# nomux1_2.net
KiCad netlist of a schematic drawn in EAGLE
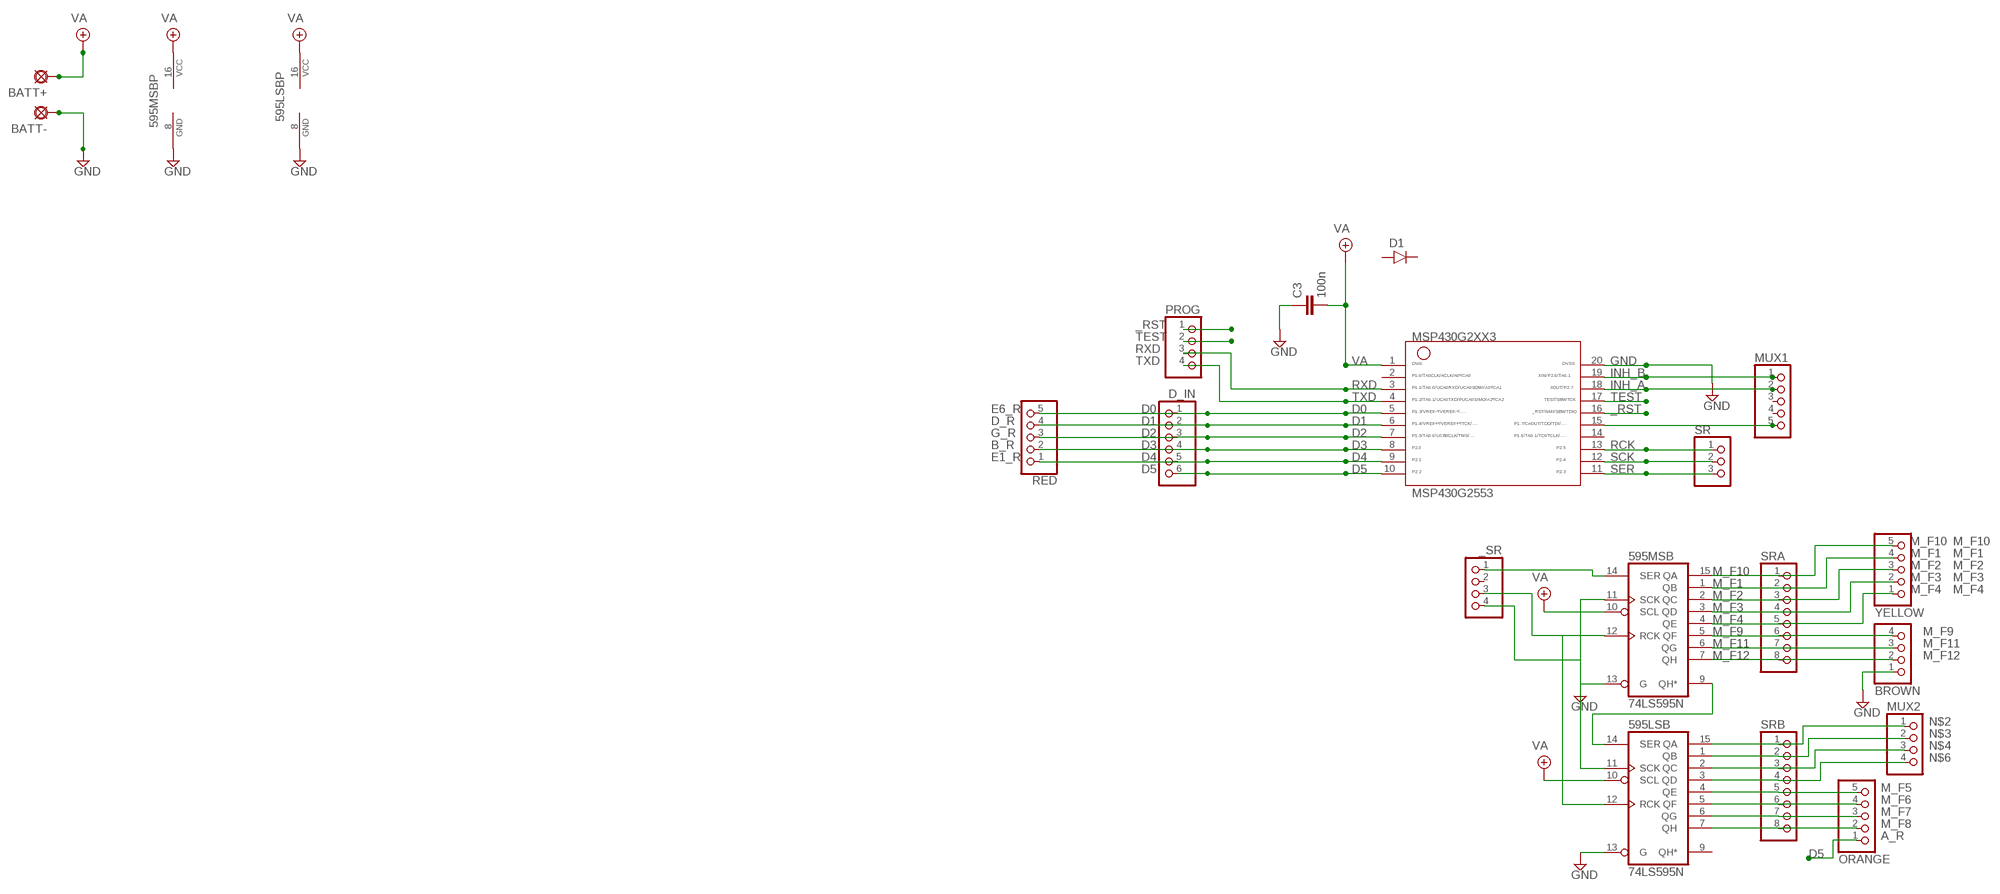
[diagram p0: schematic, sheet 1]

(export (version "E")
  (design (tool "Eeschema 10.0.6"))
  (components
    (comp (ref "595LSB")
      (value "74LS595N")
      (footprint "eagle-import:DIL16")
      (libsource (lib "eagle-import") (part "74595NLS"))
    )
    (comp (ref "595MSB")
      (value "74LS595N")
      (footprint "eagle-import:DIL16")
      (libsource (lib "eagle-import") (part "74595NLS"))
    )
    (comp (ref "BATT+")
      (value "PADL")
      (footprint "eagle-import:LONG")
      (libsource (lib "eagle-import") (part "PADL"))
    )
    (comp (ref "BATT-")
      (value "PADL")
      (footprint "eagle-import:LONG")
      (libsource (lib "eagle-import") (part "PADL"))
    )
    (comp (ref "BROWN")
      (value "PINHD-1X4")
      (footprint "eagle-import:1X04")
      (libsource (lib "eagle-import") (part "PINHD-1X4"))
    )
    (comp (ref "C3")
      (value "100n")
      (footprint "eagle-import:050X030_050_3")
      (libsource (lib "eagle-import") (part "050X030_050"))
    )
    (comp (ref "D1")
      (value "1N400X.4")
      (footprint "eagle-import:DO41-4")
      (libsource (lib "eagle-import") (part "1N400X.4"))
    )
    (comp (ref "D_IN")
      (value "PINHD-1X6")
      (footprint "eagle-import:1X06")
      (libsource (lib "eagle-import") (part "PINHD-1X6"))
    )
    (comp (ref "MSP430G2553")
      (value "G2XX3---N20")
      (footprint "eagle-import:N20")
      (libsource (lib "eagle-import") (part "G2XX3---N20"))
    )
    (comp (ref "MUX1")
      (value "PINHD-1X5")
      (footprint "eagle-import:1X05")
      (libsource (lib "eagle-import") (part "PINHD-1X5"))
    )
    (comp (ref "MUX2")
      (value "PINHD-1X4")
      (footprint "eagle-import:1X04")
      (libsource (lib "eagle-import") (part "PINHD-1X4"))
    )
    (comp (ref "ORANGE")
      (value "PINHD-1X5")
      (footprint "eagle-import:1X05")
      (libsource (lib "eagle-import") (part "PINHD-1X5"))
    )
    (comp (ref "PROG")
      (value "PINHD-1X4")
      (footprint "eagle-import:1X04")
      (libsource (lib "eagle-import") (part "PINHD-1X4"))
    )
    (comp (ref "RED")
      (value "PINHD-1X5")
      (footprint "eagle-import:1X05")
      (libsource (lib "eagle-import") (part "PINHD-1X5"))
    )
    (comp (ref "SR")
      (value "PINHD-1X3")
      (footprint "eagle-import:1X03")
      (libsource (lib "eagle-import") (part "PINHD-1X3"))
    )
    (comp (ref "SRA")
      (value "PINHD-1X8")
      (footprint "eagle-import:1X08")
      (libsource (lib "eagle-import") (part "PINHD-1X8"))
    )
    (comp (ref "SRB")
      (value "PINHD-1X8")
      (footprint "eagle-import:1X08")
      (libsource (lib "eagle-import") (part "PINHD-1X8"))
    )
    (comp (ref "YELLOW")
      (value "PINHD-1X5")
      (footprint "eagle-import:1X05")
      (libsource (lib "eagle-import") (part "PINHD-1X5"))
    )
    (comp (ref "_SR")
      (value "PINHD-1X4")
      (footprint "eagle-import:1X04")
      (libsource (lib "eagle-import") (part "PINHD-1X4"))
    )
  )
  (nets
    (net (code "1") (name "/D0") (class "Default")
      (node (ref "D_IN") (pin "1") (pinfunction "1_1") (pintype "passive"))
      (node (ref "MSP430G2553") (pin "5") (pinfunction "5_5") (pintype "bidirectional"))
      (node (ref "RED") (pin "5") (pinfunction "5_5") (pintype "passive"))
    )
    (net (code "2") (name "/D1") (class "Default")
      (node (ref "D_IN") (pin "2") (pinfunction "2_2") (pintype "passive"))
      (node (ref "MSP430G2553") (pin "6") (pinfunction "6_6") (pintype "bidirectional"))
      (node (ref "RED") (pin "4") (pinfunction "4_4") (pintype "passive"))
    )
    (net (code "3") (name "/D2") (class "Default")
      (node (ref "D_IN") (pin "3") (pinfunction "3_3") (pintype "passive"))
      (node (ref "MSP430G2553") (pin "7") (pinfunction "7_7") (pintype "bidirectional"))
      (node (ref "RED") (pin "3") (pinfunction "3_3") (pintype "passive"))
    )
    (net (code "4") (name "/D3") (class "Default")
      (node (ref "D_IN") (pin "4") (pinfunction "4_4") (pintype "passive"))
      (node (ref "MSP430G2553") (pin "8") (pinfunction "8_8") (pintype "bidirectional"))
      (node (ref "RED") (pin "2") (pinfunction "2_2") (pintype "passive"))
    )
    (net (code "5") (name "/D4") (class "Default")
      (node (ref "D_IN") (pin "5") (pinfunction "5_5") (pintype "passive"))
      (node (ref "MSP430G2553") (pin "9") (pinfunction "9_9") (pintype "bidirectional"))
      (node (ref "RED") (pin "1") (pinfunction "1_1") (pintype "passive"))
    )
    (net (code "6") (name "/D5") (class "Default")
      (node (ref "D_IN") (pin "6") (pinfunction "6_6") (pintype "passive"))
      (node (ref "MSP430G2553") (pin "10") (pinfunction "10_10") (pintype "bidirectional"))
      (node (ref "ORANGE") (pin "1") (pinfunction "1_1") (pintype "passive"))
    )
    (net (code "7") (name "/INH_A") (class "Default")
      (node (ref "MSP430G2553") (pin "18") (pinfunction "18_18") (pintype "bidirectional"))
      (node (ref "MUX1") (pin "2") (pinfunction "2_2") (pintype "passive"))
    )
    (net (code "8") (name "/INH_B") (class "Default")
      (node (ref "MSP430G2553") (pin "19") (pinfunction "19_19") (pintype "bidirectional"))
      (node (ref "MUX1") (pin "1") (pinfunction "1_1") (pintype "passive"))
    )
    (net (code "9") (name "/M_F1") (class "Default")
      (node (ref "595MSB") (pin "1") (pinfunction "QB_1") (pintype "tri_state"))
      (node (ref "SRA") (pin "2") (pinfunction "2_2") (pintype "passive"))
      (node (ref "YELLOW") (pin "4") (pinfunction "4_4") (pintype "passive"))
    )
    (net (code "10") (name "/M_F2") (class "Default")
      (node (ref "595MSB") (pin "2") (pinfunction "QC_2") (pintype "tri_state"))
      (node (ref "SRA") (pin "3") (pinfunction "3_3") (pintype "passive"))
      (node (ref "YELLOW") (pin "3") (pinfunction "3_3") (pintype "passive"))
    )
    (net (code "11") (name "/M_F3") (class "Default")
      (node (ref "595MSB") (pin "3") (pinfunction "QD_3") (pintype "tri_state"))
      (node (ref "SRA") (pin "4") (pinfunction "4_4") (pintype "passive"))
      (node (ref "YELLOW") (pin "2") (pinfunction "2_2") (pintype "passive"))
    )
    (net (code "12") (name "/M_F4") (class "Default")
      (node (ref "595MSB") (pin "4") (pinfunction "QE_4") (pintype "tri_state"))
      (node (ref "SRA") (pin "5") (pinfunction "5_5") (pintype "passive"))
      (node (ref "YELLOW") (pin "1") (pinfunction "1_1") (pintype "passive"))
    )
    (net (code "13") (name "/M_F5") (class "Default")
      (node (ref "595LSB") (pin "4") (pinfunction "QE_4") (pintype "tri_state"))
      (node (ref "ORANGE") (pin "5") (pinfunction "5_5") (pintype "passive"))
      (node (ref "SRB") (pin "5") (pinfunction "5_5") (pintype "passive"))
    )
    (net (code "14") (name "/M_F6") (class "Default")
      (node (ref "595LSB") (pin "5") (pinfunction "QF_5") (pintype "tri_state"))
      (node (ref "ORANGE") (pin "4") (pinfunction "4_4") (pintype "passive"))
      (node (ref "SRB") (pin "6") (pinfunction "6_6") (pintype "passive"))
    )
    (net (code "15") (name "/M_F7") (class "Default")
      (node (ref "595LSB") (pin "6") (pinfunction "QG_6") (pintype "tri_state"))
      (node (ref "ORANGE") (pin "3") (pinfunction "3_3") (pintype "passive"))
      (node (ref "SRB") (pin "7") (pinfunction "7_7") (pintype "passive"))
    )
    (net (code "16") (name "/M_F8") (class "Default")
      (node (ref "595LSB") (pin "7") (pinfunction "QH_7") (pintype "tri_state"))
      (node (ref "ORANGE") (pin "2") (pinfunction "2_2") (pintype "passive"))
      (node (ref "SRB") (pin "8") (pinfunction "8_8") (pintype "passive"))
    )
    (net (code "17") (name "/M_F9") (class "Default")
      (node (ref "595MSB") (pin "5") (pinfunction "QF_5") (pintype "tri_state"))
      (node (ref "BROWN") (pin "4") (pinfunction "4_4") (pintype "passive"))
      (node (ref "SRA") (pin "6") (pinfunction "6_6") (pintype "passive"))
    )
    (net (code "18") (name "/M_F10") (class "Default")
      (node (ref "595MSB") (pin "15") (pinfunction "QA_15") (pintype "tri_state"))
      (node (ref "SRA") (pin "1") (pinfunction "1_1") (pintype "passive"))
      (node (ref "YELLOW") (pin "5") (pinfunction "5_5") (pintype "passive"))
    )
    (net (code "19") (name "/M_F11") (class "Default")
      (node (ref "595MSB") (pin "6") (pinfunction "QG_6") (pintype "tri_state"))
      (node (ref "BROWN") (pin "3") (pinfunction "3_3") (pintype "passive"))
      (node (ref "SRA") (pin "7") (pinfunction "7_7") (pintype "passive"))
    )
    (net (code "20") (name "/M_F12") (class "Default")
      (node (ref "595MSB") (pin "7") (pinfunction "QH_7") (pintype "tri_state"))
      (node (ref "BROWN") (pin "2") (pinfunction "2_2") (pintype "passive"))
      (node (ref "SRA") (pin "8") (pinfunction "8_8") (pintype "passive"))
    )
    (net (code "21") (name "/N$2") (class "Default")
      (node (ref "595LSB") (pin "15") (pinfunction "QA_15") (pintype "tri_state"))
      (node (ref "MUX2") (pin "1") (pinfunction "1_1") (pintype "passive"))
      (node (ref "SRB") (pin "1") (pinfunction "1_1") (pintype "passive"))
    )
    (net (code "22") (name "/N$3") (class "Default")
      (node (ref "595LSB") (pin "1") (pinfunction "QB_1") (pintype "tri_state"))
      (node (ref "MUX2") (pin "2") (pinfunction "2_2") (pintype "passive"))
      (node (ref "SRB") (pin "2") (pinfunction "2_2") (pintype "passive"))
    )
    (net (code "23") (name "/N$4") (class "Default")
      (node (ref "595LSB") (pin "2") (pinfunction "QC_2") (pintype "tri_state"))
      (node (ref "MUX2") (pin "3") (pinfunction "3_3") (pintype "passive"))
      (node (ref "SRB") (pin "3") (pinfunction "3_3") (pintype "passive"))
    )
    (net (code "24") (name "/N$6") (class "Default")
      (node (ref "595LSB") (pin "3") (pinfunction "QD_3") (pintype "tri_state"))
      (node (ref "MUX2") (pin "4") (pinfunction "4_4") (pintype "passive"))
      (node (ref "SRB") (pin "4") (pinfunction "4_4") (pintype "passive"))
    )
    (net (code "25") (name "/RCK") (class "Default")
      (node (ref "MSP430G2553") (pin "13") (pinfunction "13_13") (pintype "bidirectional"))
      (node (ref "SR") (pin "1") (pinfunction "1_1") (pintype "passive"))
    )
    (net (code "26") (name "/RXD") (class "Default")
      (node (ref "MSP430G2553") (pin "3") (pinfunction "3_3") (pintype "bidirectional"))
      (node (ref "PROG") (pin "3") (pinfunction "3_3") (pintype "passive"))
    )
    (net (code "27") (name "/SCK") (class "Default")
      (node (ref "MSP430G2553") (pin "12") (pinfunction "12_12") (pintype "bidirectional"))
      (node (ref "SR") (pin "2") (pinfunction "2_2") (pintype "passive"))
    )
    (net (code "28") (name "/SER") (class "Default")
      (node (ref "MSP430G2553") (pin "11") (pinfunction "11_11") (pintype "bidirectional"))
      (node (ref "SR") (pin "3") (pinfunction "3_3") (pintype "passive"))
    )
    (net (code "29") (name "/TEST") (class "Default")
      (node (ref "MSP430G2553") (pin "17") (pinfunction "17_17") (pintype "bidirectional"))
      (node (ref "PROG") (pin "2") (pinfunction "2_2") (pintype "passive"))
    )
    (net (code "30") (name "/TXD") (class "Default")
      (node (ref "MSP430G2553") (pin "4") (pinfunction "4_4") (pintype "bidirectional"))
      (node (ref "PROG") (pin "4") (pinfunction "4_4") (pintype "passive"))
    )
    (net (code "31") (name "/_RST") (class "Default")
      (node (ref "MSP430G2553") (pin "16") (pinfunction "16_16") (pintype "bidirectional"))
      (node (ref "PROG") (pin "1") (pinfunction "1_1") (pintype "passive"))
    )
    (net (code "32") (name "GND") (class "Default")
      (node (ref "595LSB") (pin "13") (pinfunction "G_13") (pintype "input"))
      (node (ref "595LSB") (pin "8") (pinfunction "GND_8") (pintype "power_in"))
      (node (ref "595MSB") (pin "13") (pinfunction "G_13") (pintype "input"))
      (node (ref "595MSB") (pin "8") (pinfunction "GND_8") (pintype "power_in"))
      (node (ref "BATT-") (pin "1") (pinfunction "PAD_1") (pintype "passive"))
      (node (ref "BROWN") (pin "1") (pinfunction "1_1") (pintype "passive"))
      (node (ref "C3") (pin "1") (pinfunction "1_1") (pintype "passive"))
      (node (ref "MSP430G2553") (pin "20") (pinfunction "20_20") (pintype "bidirectional"))
    )
    (net (code "33") (name "Net-(595LSBA-RCK)") (class "Default")
      (node (ref "595LSB") (pin "12") (pinfunction "RCK_12") (pintype "input"))
      (node (ref "595MSB") (pin "12") (pinfunction "RCK_12") (pintype "input"))
      (node (ref "_SR") (pin "3") (pinfunction "3_3") (pintype "passive"))
    )
    (net (code "34") (name "Net-(595LSBA-SCK)") (class "Default")
      (node (ref "595LSB") (pin "11") (pinfunction "SCK_11") (pintype "input"))
      (node (ref "595MSB") (pin "11") (pinfunction "SCK_11") (pintype "input"))
      (node (ref "_SR") (pin "4") (pinfunction "4_4") (pintype "passive"))
    )
    (net (code "35") (name "Net-(595LSBA-SER)") (class "Default")
      (node (ref "595LSB") (pin "14") (pinfunction "SER_14") (pintype "input"))
      (node (ref "595MSB") (pin "9") (pinfunction "QH*_9") (pintype "tri_state"))
    )
    (net (code "36") (name "Net-(595MSBA-SER)") (class "Default")
      (node (ref "595MSB") (pin "14") (pinfunction "SER_14") (pintype "input"))
      (node (ref "_SR") (pin "1") (pinfunction "1_1") (pintype "passive"))
    )
    (net (code "37") (name "Net-(MSP430G2553-Pad15)") (class "Default")
      (node (ref "MSP430G2553") (pin "15") (pinfunction "15_15") (pintype "bidirectional"))
      (node (ref "MUX1") (pin "5") (pinfunction "5_5") (pintype "passive"))
    )
    (net (code "38") (name "VA") (class "Default")
      (node (ref "595LSB") (pin "10") (pinfunction "SCL_10") (pintype "input"))
      (node (ref "595LSB") (pin "16") (pinfunction "VCC_16") (pintype "power_in"))
      (node (ref "595MSB") (pin "10") (pinfunction "SCL_10") (pintype "input"))
      (node (ref "595MSB") (pin "16") (pinfunction "VCC_16") (pintype "power_in"))
      (node (ref "BATT+") (pin "1") (pinfunction "PAD_1") (pintype "passive"))
      (node (ref "C3") (pin "2") (pinfunction "2_2") (pintype "passive"))
      (node (ref "MSP430G2553") (pin "1") (pinfunction "1_1") (pintype "bidirectional"))
    )
    (net (code "39") (name "unconnected-(595LSBA-QH*-Pad9)") (class "Default")
      (node (ref "595LSB") (pin "9") (pinfunction "QH*_9") (pintype "tri_state"))
    )
    (net (code "40") (name "unconnected-(D1-PadA)") (class "Default")
      (node (ref "D1") (pin "A") (pinfunction "A_A") (pintype "passive"))
    )
    (net (code "41") (name "unconnected-(D1-PadC)") (class "Default")
      (node (ref "D1") (pin "C") (pinfunction "C_C") (pintype "passive"))
    )
    (net (code "42") (name "unconnected-(MSP430G2553-Pad2)") (class "Default")
      (node (ref "MSP430G2553") (pin "2") (pinfunction "2_2") (pintype "bidirectional"))
    )
    (net (code "43") (name "unconnected-(MSP430G2553-Pad14)") (class "Default")
      (node (ref "MSP430G2553") (pin "14") (pinfunction "14_14") (pintype "bidirectional"))
    )
    (net (code "44") (name "unconnected-(MUX1-Pad3)") (class "Default")
      (node (ref "MUX1") (pin "3") (pinfunction "3_3") (pintype "passive"))
    )
    (net (code "45") (name "unconnected-(MUX1-Pad4)") (class "Default")
      (node (ref "MUX1") (pin "4") (pinfunction "4_4") (pintype "passive"))
    )
    (net (code "46") (name "unconnected-(_SR-Pad2)") (class "Default")
      (node (ref "_SR") (pin "2") (pinfunction "2_2") (pintype "passive"))
    )
  )
)
